# Memory.net
KiCad netlist of a schematic drawn in Altium Designer
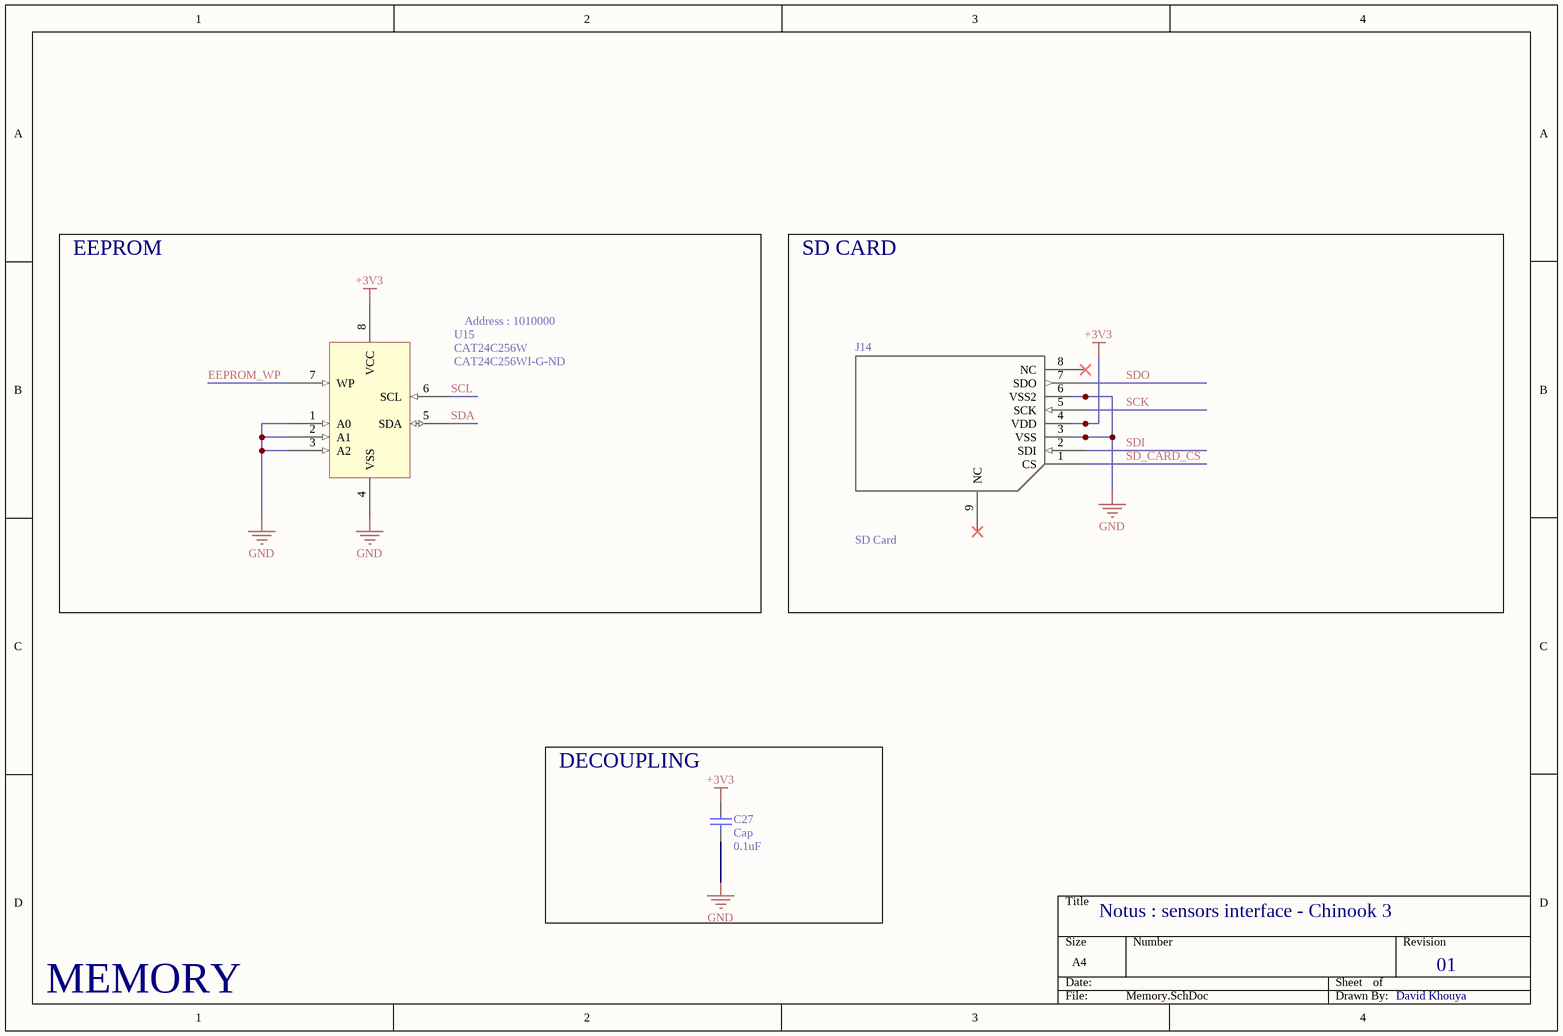
[diagram p0: Memory.SchDoc]

(export (version "E")
  (design (tool "Eeschema 10.0.6"))
  (components
    (comp (ref "C27")
      (value "Cap")
      (footprint "RESC2012N")
      (description "Capacitor")
      (fields (field (name "ALTIUM_VALUE") "0.1uF") (field (name "PUBLISHER") "Altium Limited"))
      (libsource (lib "Miscellaneous Devices") (part "Cap"))
    )
    (comp (ref "J14")
      (value "SD Card")
      (footprint "SD Card")
      (description "SPI Sd card connector pinout")
      (libsource (lib "dkhouya") (part "SD Card"))
    )
    (comp (ref "U15")
      (value "CAT24C256W")
      (footprint "8SOIC-2")
      (description "256 kb I2C CMOS Serial  EEPROM")
      (fields (field (name "SUPPLIER PART NUMBER 1") "CAT24C256WI-G-ND"))
      (libsource (lib "dkhouya") (part "CAT24C256W"))
    )
  )
  (nets
    (net (code "1") (name "+3V3") (class "Default")
      (node (ref "C27") (pin "2") (pinfunction "2_2") (pintype "passive"))
      (node (ref "J14") (pin "4") (pinfunction "VDD_4") (pintype "power_in"))
      (node (ref "U15") (pin "8") (pinfunction "VCC_8") (pintype "power_in"))
    )
    (net (code "2") (name "/EEPROM_WP") (class "Default")
      (node (ref "U15") (pin "7") (pinfunction "WP_7") (pintype "input"))
    )
    (net (code "3") (name "/SCK") (class "Default")
      (node (ref "J14") (pin "5") (pinfunction "SCK_5") (pintype "input"))
    )
    (net (code "4") (name "/SCL") (class "Default")
      (node (ref "U15") (pin "6") (pinfunction "SCL_6") (pintype "input"))
    )
    (net (code "5") (name "/SDA") (class "Default")
      (node (ref "U15") (pin "5") (pinfunction "SDA_5") (pintype "bidirectional"))
    )
    (net (code "6") (name "/SDI") (class "Default")
      (node (ref "J14") (pin "2") (pinfunction "SDI_2") (pintype "input"))
    )
    (net (code "7") (name "/SDO") (class "Default")
      (node (ref "J14") (pin "7") (pinfunction "SDO_7") (pintype "output"))
    )
    (net (code "8") (name "/SD_CARD_CS") (class "Default")
      (node (ref "J14") (pin "1") (pinfunction "CS_1") (pintype "passive"))
    )
    (net (code "9") (name "GND") (class "Default")
      (node (ref "C27") (pin "1") (pinfunction "1_1") (pintype "passive"))
      (node (ref "J14") (pin "3") (pinfunction "VSS_3") (pintype "power_in"))
      (node (ref "J14") (pin "6") (pinfunction "VSS2_6") (pintype "power_in"))
      (node (ref "U15") (pin "1") (pinfunction "A0_1") (pintype "input"))
      (node (ref "U15") (pin "2") (pinfunction "A1_2") (pintype "input"))
      (node (ref "U15") (pin "3") (pinfunction "A2_3") (pintype "input"))
      (node (ref "U15") (pin "4") (pinfunction "VSS_4") (pintype "passive"))
    )
    (net (code "10") (name "unconnected-(J14-NC-Pad8)") (class "Default")
      (node (ref "J14") (pin "8") (pinfunction "NC_8") (pintype "passive+no_connect"))
    )
    (net (code "11") (name "unconnected-(J14-NC-Pad9)") (class "Default")
      (node (ref "J14") (pin "9") (pinfunction "NC_9") (pintype "passive+no_connect"))
    )
  )
)
